# btn_0_3.net
KiCad netlist of a schematic drawn in EAGLE
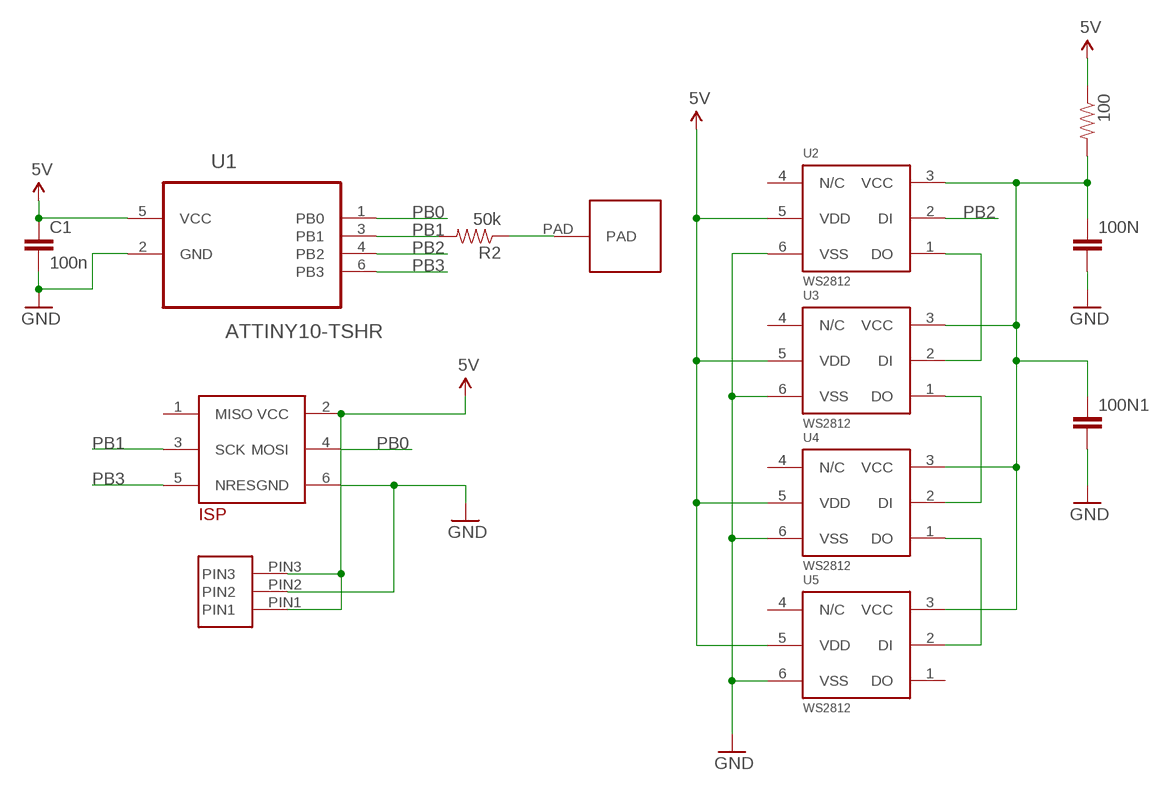
[diagram p0: schematic, sheet 1]

(export (version "E")
  (design (tool "Eeschema 10.0.6"))
  (components
    (comp (ref "100")
      (value "RESISTOR0805-RES")
      (footprint "eagle-import:0805")
      (libsource (lib "eagle-import") (part "RESISTOR0805-RES"))
    )
    (comp (ref "100N")
      (value "CAP0805")
      (footprint "eagle-import:0805")
      (libsource (lib "eagle-import") (part "CAP0805"))
    )
    (comp (ref "100N1")
      (value "CAP0805")
      (footprint "eagle-import:0805")
      (libsource (lib "eagle-import") (part "CAP0805"))
    )
    (comp (ref "C1")
      (value "100n")
      (footprint "eagle-import:0805")
      (libsource (lib "eagle-import") (part "CAP0805"))
    )
    (comp (ref "R2")
      (value "50k")
      (footprint "eagle-import:0805")
      (libsource (lib "eagle-import") (part "RESISTOR0805-RES"))
    )
    (comp (ref "U$1")
      (value "TB_ISPEDGE_2X3")
      (footprint "eagle-import:ISP_EDGE2X3")
      (libsource (lib "eagle-import") (part "TB_ISPEDGE_2X3"))
    )
    (comp (ref "U$2")
      (value "TB_TOUCH_0.5INCH")
      (footprint "eagle-import:TOUCH_ROUND0.5INCH")
      (libsource (lib "eagle-import") (part "TB_TOUCH_0.5INCH"))
    )
    (comp (ref "U$4")
      (value "TB_EDGE3")
      (footprint "eagle-import:TB_EDGE3")
      (libsource (lib "eagle-import") (part "TB_EDGE3"))
    )
    (comp (ref "U1")
      (value "ATTINY10-TSHR")
      (footprint "eagle-import:SOT95P280X145-6N")
      (libsource (lib "eagle-import") (part "ATTINY10-TSHR"))
    )
    (comp (ref "U2")
      (value "WS2812")
      (footprint "eagle-import:PLCC6")
      (libsource (lib "eagle-import") (part "WS2812"))
    )
    (comp (ref "U3")
      (value "WS2812")
      (footprint "eagle-import:PLCC6")
      (libsource (lib "eagle-import") (part "WS2812"))
    )
    (comp (ref "U4")
      (value "WS2812")
      (footprint "eagle-import:PLCC6")
      (libsource (lib "eagle-import") (part "WS2812"))
    )
    (comp (ref "U5")
      (value "WS2812")
      (footprint "eagle-import:PLCC6")
      (libsource (lib "eagle-import") (part "WS2812"))
    )
  )
  (nets
    (net (code "1") (name "/PB0") (class "Default")
      (node (ref "U$1") (pin "4") (pinfunction "MOSI_4") (pintype "bidirectional"))
      (node (ref "U1") (pin "1") (pinfunction "PB0_1") (pintype "bidirectional"))
    )
    (net (code "2") (name "/PB1") (class "Default")
      (node (ref "R2") (pin "2") (pinfunction "2_2") (pintype "passive"))
      (node (ref "U$1") (pin "3") (pinfunction "SCK_3") (pintype "bidirectional"))
      (node (ref "U1") (pin "3") (pinfunction "PB1_3") (pintype "bidirectional"))
    )
    (net (code "3") (name "/PB2") (class "Default")
      (node (ref "U1") (pin "4") (pinfunction "PB2_4") (pintype "bidirectional"))
      (node (ref "U2") (pin "2") (pinfunction "DI_2") (pintype "input"))
    )
    (net (code "4") (name "/PB3") (class "Default")
      (node (ref "U$1") (pin "5") (pinfunction "NRES_5") (pintype "bidirectional"))
      (node (ref "U1") (pin "6") (pinfunction "PB3_6") (pintype "bidirectional"))
    )
    (net (code "5") (name "5V") (class "Default")
      (node (ref "100") (pin "1") (pinfunction "1_1") (pintype "passive"))
      (node (ref "C1") (pin "1") (pinfunction "1_1") (pintype "passive"))
      (node (ref "U$1") (pin "2") (pinfunction "VCC_2") (pintype "bidirectional"))
      (node (ref "U$4") (pin "PIN1") (pinfunction "PIN1_PIN1") (pintype "bidirectional"))
      (node (ref "U$4") (pin "PIN3") (pinfunction "PIN3_PIN3") (pintype "bidirectional"))
      (node (ref "U1") (pin "5") (pinfunction "VCC_5") (pintype "power_in"))
      (node (ref "U2") (pin "5") (pinfunction "VDD_5") (pintype "power_in"))
      (node (ref "U3") (pin "5") (pinfunction "VDD_5") (pintype "power_in"))
      (node (ref "U4") (pin "5") (pinfunction "VDD_5") (pintype "power_in"))
      (node (ref "U5") (pin "5") (pinfunction "VDD_5") (pintype "power_in"))
    )
    (net (code "6") (name "GND") (class "Default")
      (node (ref "100N") (pin "2") (pinfunction "2_2") (pintype "passive"))
      (node (ref "100N1") (pin "2") (pinfunction "2_2") (pintype "passive"))
      (node (ref "C1") (pin "2") (pinfunction "2_2") (pintype "passive"))
      (node (ref "U$1") (pin "6") (pinfunction "GND_6") (pintype "bidirectional"))
      (node (ref "U$4") (pin "PIN2") (pinfunction "PIN2_PIN2") (pintype "bidirectional"))
      (node (ref "U1") (pin "2") (pinfunction "GND_2") (pintype "passive"))
      (node (ref "U2") (pin "6") (pinfunction "VSS_6") (pintype "power_in"))
      (node (ref "U3") (pin "6") (pinfunction "VSS_6") (pintype "power_in"))
      (node (ref "U4") (pin "6") (pinfunction "VSS_6") (pintype "power_in"))
      (node (ref "U5") (pin "6") (pinfunction "VSS_6") (pintype "power_in"))
    )
    (net (code "7") (name "Net-(R2-Pad1)") (class "Default")
      (node (ref "R2") (pin "1") (pinfunction "1_1") (pintype "passive"))
      (node (ref "U$2") (pin "PAD") (pinfunction "PAD_PAD") (pintype "bidirectional"))
    )
    (net (code "8") (name "Net-(U2-DO)") (class "Default")
      (node (ref "U2") (pin "1") (pinfunction "DO_1") (pintype "output"))
      (node (ref "U3") (pin "2") (pinfunction "DI_2") (pintype "input"))
    )
    (net (code "9") (name "Net-(U2-VCC)") (class "Default")
      (node (ref "100") (pin "2") (pinfunction "2_2") (pintype "passive"))
      (node (ref "100N") (pin "1") (pinfunction "1_1") (pintype "passive"))
      (node (ref "100N1") (pin "1") (pinfunction "1_1") (pintype "passive"))
      (node (ref "U2") (pin "3") (pinfunction "VCC_3") (pintype "power_in"))
      (node (ref "U3") (pin "3") (pinfunction "VCC_3") (pintype "power_in"))
      (node (ref "U4") (pin "3") (pinfunction "VCC_3") (pintype "power_in"))
      (node (ref "U5") (pin "3") (pinfunction "VCC_3") (pintype "power_in"))
    )
    (net (code "10") (name "Net-(U3-DO)") (class "Default")
      (node (ref "U3") (pin "1") (pinfunction "DO_1") (pintype "output"))
      (node (ref "U4") (pin "2") (pinfunction "DI_2") (pintype "input"))
    )
    (net (code "11") (name "Net-(U4-DO)") (class "Default")
      (node (ref "U4") (pin "1") (pinfunction "DO_1") (pintype "output"))
      (node (ref "U5") (pin "2") (pinfunction "DI_2") (pintype "input"))
    )
    (net (code "12") (name "unconnected-(U$1-MISO-Pad1)") (class "Default")
      (node (ref "U$1") (pin "1") (pinfunction "MISO_1") (pintype "bidirectional"))
    )
    (net (code "13") (name "unconnected-(U2-N{slash}C-Pad4)") (class "Default")
      (node (ref "U2") (pin "4") (pinfunction "N/C_4") (pintype "bidirectional"))
    )
    (net (code "14") (name "unconnected-(U3-N{slash}C-Pad4)") (class "Default")
      (node (ref "U3") (pin "4") (pinfunction "N/C_4") (pintype "bidirectional"))
    )
    (net (code "15") (name "unconnected-(U4-N{slash}C-Pad4)") (class "Default")
      (node (ref "U4") (pin "4") (pinfunction "N/C_4") (pintype "bidirectional"))
    )
    (net (code "16") (name "unconnected-(U5-DO-Pad1)") (class "Default")
      (node (ref "U5") (pin "1") (pinfunction "DO_1") (pintype "output"))
    )
    (net (code "17") (name "unconnected-(U5-N{slash}C-Pad4)") (class "Default")
      (node (ref "U5") (pin "4") (pinfunction "N/C_4") (pintype "bidirectional"))
    )
  )
)
